# BHOnOfreSquareBoard.net
KiCad netlist of a schematic drawn in EAGLE
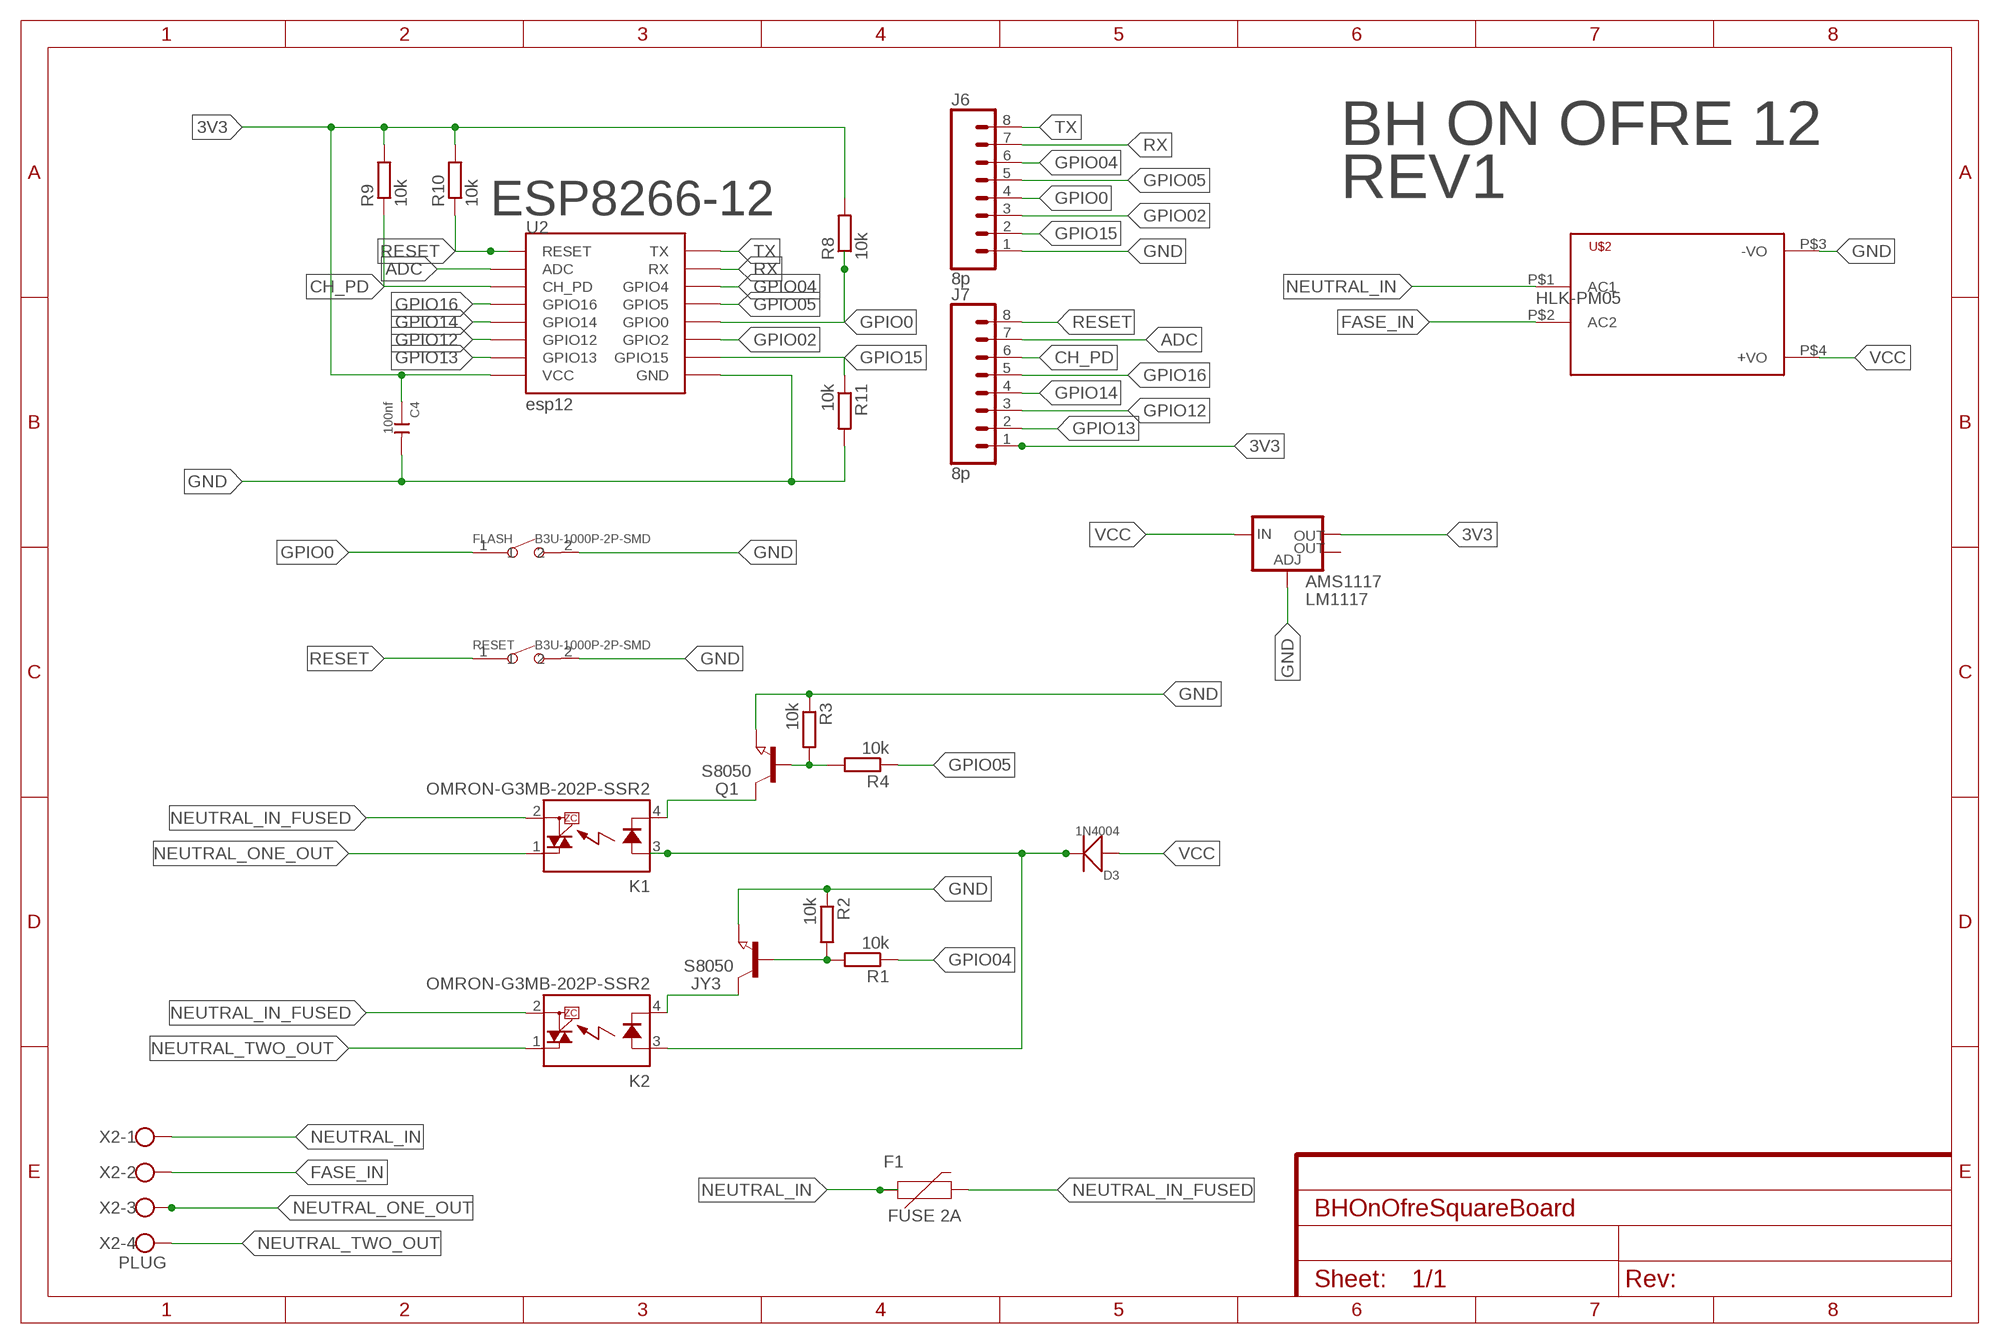
[diagram p0: schematic, sheet 1]

(export (version "E")
  (design (tool "Eeschema 10.0.6"))
  (components
    (comp (ref "AMS1117")
      (value "LM1117")
      (footprint "eagle-import:SOT223")
      (libsource (lib "eagle-import") (part "V_REG_LM1117SOT223"))
    )
    (comp (ref "C4")
      (value "100nf")
      (footprint "eagle-import:C0805")
      (fields (field (name "MPN") "CC0805KRX7R9BB104"))
      (libsource (lib "eagle-import") (part "CERAMIC-100NF-50V-10%-X7R(0805)"))
    )
    (comp (ref "D3")
      (value "1N4004")
      (footprint "eagle-import:DO-214AC")
      (fields (field (name "MPN") "1N4007"))
      (libsource (lib "eagle-import") (part "DIODE-GEN-PURPOSE-1KV-1A(DO-214AC)"))
    )
    (comp (ref "F1")
      (value "FUSE 2A")
      (footprint "eagle-import:PTH")
      (libsource (lib "eagle-import") (part "PPTC_PTH"))
    )
    (comp (ref "FLASH")
      (value "B3U-1000P-2P-SMD")
      (footprint "eagle-import:SW2-2.6-3.0X2.5X1.2+0.4MM")
      (libsource (lib "eagle-import") (part "SMD-BUTTON(2P-3.0X2.5X1.2+0.4MM)-B3U-1000P-2P-SMD"))
    )
    (comp (ref "J6")
      (value "8p")
      (footprint "eagle-import:1X08")
      (libsource (lib "eagle-import") (part "CONN_08{dblquote}"))
    )
    (comp (ref "J7")
      (value "8p")
      (footprint "eagle-import:1X08")
      (libsource (lib "eagle-import") (part "CONN_08{dblquote}"))
    )
    (comp (ref "JY3")
      (value "S8050")
      (footprint "eagle-import:SOT23")
      (libsource (lib "eagle-import") (part "NPN-TRANSISTOR_SOT23"))
    )
    (comp (ref "K1")
      (value "OMRON-G3MB-202P-SSR2")
      (footprint "eagle-import:OMRON-G3MB-202P-SSR")
      (fields (field (name "MPN") "S202S02F"))
      (libsource (lib "eagle-import") (part "OMRON-G3MB-202P-SSR2"))
    )
    (comp (ref "K2")
      (value "OMRON-G3MB-202P-SSR2")
      (footprint "eagle-import:OMRON-G3MB-202P-SSR")
      (fields (field (name "MPN") "S202S02F"))
      (libsource (lib "eagle-import") (part "OMRON-G3MB-202P-SSR2"))
    )
    (comp (ref "Q1")
      (value "S8050")
      (footprint "eagle-import:SOT23")
      (libsource (lib "eagle-import") (part "NPN-TRANSISTOR_SOT23"))
    )
    (comp (ref "R1")
      (value "10k")
      (footprint "eagle-import:R0603")
      (libsource (lib "eagle-import") (part "R-EU_R0603"))
    )
    (comp (ref "R2")
      (value "10k")
      (footprint "eagle-import:R0603")
      (libsource (lib "eagle-import") (part "R-EU_R0603"))
    )
    (comp (ref "R3")
      (value "10k")
      (footprint "eagle-import:R0603")
      (libsource (lib "eagle-import") (part "R-EU_R0603"))
    )
    (comp (ref "R4")
      (value "10k")
      (footprint "eagle-import:R0603")
      (libsource (lib "eagle-import") (part "R-EU_R0603"))
    )
    (comp (ref "R8")
      (value "10k")
      (footprint "eagle-import:R0603")
      (libsource (lib "eagle-import") (part "R-EU_R0603"))
    )
    (comp (ref "R9")
      (value "10k")
      (footprint "eagle-import:R0603")
      (libsource (lib "eagle-import") (part "R-EU_R0603"))
    )
    (comp (ref "R10")
      (value "10k")
      (footprint "eagle-import:R0603")
      (libsource (lib "eagle-import") (part "R-EU_R0603"))
    )
    (comp (ref "R11")
      (value "10k")
      (footprint "eagle-import:R0603")
      (libsource (lib "eagle-import") (part "R-EU_R0603"))
    )
    (comp (ref "RESET")
      (value "B3U-1000P-2P-SMD")
      (footprint "eagle-import:SW2-2.6-3.0X2.5X1.2+0.4MM")
      (libsource (lib "eagle-import") (part "SMD-BUTTON(2P-3.0X2.5X1.2+0.4MM)-B3U-1000P-2P-SMD"))
    )
    (comp (ref "U$2")
      (value "HKLPM01")
      (footprint "eagle-import:HKLPM01")
      (libsource (lib "eagle-import") (part "HKLPM01"))
    )
    (comp (ref "U2")
      (value "esp12")
      (footprint "eagle-import:ESP12-SMD")
      (libsource (lib "eagle-import") (part "ESP12SMD"))
    )
    (comp (ref "X2")
      (value "PLUG")
      (footprint "eagle-import:W237-4")
      (libsource (lib "eagle-import") (part "W237-4"))
    )
  )
  (nets
    (net (code "1") (name "3V3") (class "Default")
      (node (ref "AMS1117") (pin "2") (pinfunction "OUT_2") (pintype "output"))
      (node (ref "C4") (pin "1") (pinfunction "1_1") (pintype "passive"))
      (node (ref "J7") (pin "1") (pinfunction "1_1") (pintype "passive"))
      (node (ref "R10") (pin "2") (pinfunction "2_2") (pintype "passive"))
      (node (ref "R8") (pin "2") (pinfunction "2_2") (pintype "passive"))
      (node (ref "R9") (pin "2") (pinfunction "2_2") (pintype "passive"))
      (node (ref "U2") (pin "VCC") (pinfunction "VCC_VCC") (pintype "bidirectional"))
    )
    (net (code "2") (name "ADC") (class "Default")
      (node (ref "J7") (pin "7") (pinfunction "7_7") (pintype "passive"))
      (node (ref "U2") (pin "ADC") (pinfunction "ADC_ADC") (pintype "bidirectional"))
    )
    (net (code "3") (name "CH_PD") (class "Default")
      (node (ref "J7") (pin "6") (pinfunction "6_6") (pintype "passive"))
      (node (ref "R9") (pin "1") (pinfunction "1_1") (pintype "passive"))
      (node (ref "U2") (pin "CH_PD") (pinfunction "CH_PD_CH_PD") (pintype "bidirectional"))
    )
    (net (code "4") (name "FASE_IN") (class "Default")
      (node (ref "U$2") (pin "P$2") (pinfunction "AC2_P$2") (pintype "bidirectional"))
      (node (ref "X2") (pin "2") (pinfunction "KL_2") (pintype "passive"))
    )
    (net (code "5") (name "GND") (class "Default")
      (node (ref "AMS1117") (pin "1") (pinfunction "ADJ_1") (pintype "input"))
      (node (ref "C4") (pin "2") (pinfunction "2_2") (pintype "passive"))
      (node (ref "FLASH") (pin "2") (pinfunction "2_2") (pintype "bidirectional"))
      (node (ref "J6") (pin "1") (pinfunction "1_1") (pintype "passive"))
      (node (ref "JY3") (pin "2") (pinfunction "E_2") (pintype "passive"))
      (node (ref "Q1") (pin "2") (pinfunction "E_2") (pintype "passive"))
      (node (ref "R11") (pin "2") (pinfunction "2_2") (pintype "passive"))
      (node (ref "R2") (pin "1") (pinfunction "1_1") (pintype "passive"))
      (node (ref "R3") (pin "1") (pinfunction "1_1") (pintype "passive"))
      (node (ref "RESET") (pin "2") (pinfunction "2_2") (pintype "bidirectional"))
      (node (ref "U$2") (pin "P$3") (pinfunction "-VO_P$3") (pintype "bidirectional"))
      (node (ref "U2") (pin "GND") (pinfunction "GND_GND") (pintype "bidirectional"))
    )
    (net (code "6") (name "GPIO0") (class "Default")
      (node (ref "FLASH") (pin "1") (pinfunction "1_1") (pintype "bidirectional"))
      (node (ref "J6") (pin "4") (pinfunction "4_4") (pintype "passive"))
      (node (ref "R8") (pin "1") (pinfunction "1_1") (pintype "passive"))
      (node (ref "U2") (pin "GPIO0") (pinfunction "GPIO0_GPIO0") (pintype "bidirectional"))
    )
    (net (code "7") (name "GPIO02") (class "Default")
      (node (ref "J6") (pin "3") (pinfunction "3_3") (pintype "passive"))
      (node (ref "U2") (pin "GPIO2") (pinfunction "GPIO2_GPIO2") (pintype "bidirectional"))
    )
    (net (code "8") (name "GPIO04") (class "Default")
      (node (ref "J6") (pin "6") (pinfunction "6_6") (pintype "passive"))
      (node (ref "R1") (pin "1") (pinfunction "1_1") (pintype "passive"))
      (node (ref "U2") (pin "GPIO4") (pinfunction "GPIO4_GPIO4") (pintype "bidirectional"))
    )
    (net (code "9") (name "GPIO05") (class "Default")
      (node (ref "J6") (pin "5") (pinfunction "5_5") (pintype "passive"))
      (node (ref "R4") (pin "1") (pinfunction "1_1") (pintype "passive"))
      (node (ref "U2") (pin "GPIO5") (pinfunction "GPIO5_GPIO5") (pintype "bidirectional"))
    )
    (net (code "10") (name "GPIO12") (class "Default")
      (node (ref "J7") (pin "3") (pinfunction "3_3") (pintype "passive"))
      (node (ref "U2") (pin "GPIO12") (pinfunction "GPIO12_GPIO12") (pintype "bidirectional"))
    )
    (net (code "11") (name "GPIO13") (class "Default")
      (node (ref "J7") (pin "2") (pinfunction "2_2") (pintype "passive"))
      (node (ref "U2") (pin "GPIO13") (pinfunction "GPIO13_GPIO13") (pintype "bidirectional"))
    )
    (net (code "12") (name "GPIO14") (class "Default")
      (node (ref "J7") (pin "4") (pinfunction "4_4") (pintype "passive"))
      (node (ref "U2") (pin "GPIO14") (pinfunction "GPIO14_GPIO14") (pintype "bidirectional"))
    )
    (net (code "13") (name "GPIO15") (class "Default")
      (node (ref "J6") (pin "2") (pinfunction "2_2") (pintype "passive"))
      (node (ref "R11") (pin "1") (pinfunction "1_1") (pintype "passive"))
      (node (ref "U2") (pin "GPIO15") (pinfunction "GPIO15_GPIO15") (pintype "bidirectional"))
    )
    (net (code "14") (name "GPIO16") (class "Default")
      (node (ref "J7") (pin "5") (pinfunction "5_5") (pintype "passive"))
      (node (ref "U2") (pin "GPIO16") (pinfunction "GPIO16_GPIO16") (pintype "bidirectional"))
    )
    (net (code "15") (name "NEUTRAL_IN") (class "Default")
      (node (ref "F1") (pin "P$1") (pinfunction "1_P$1") (pintype "bidirectional"))
      (node (ref "U$2") (pin "P$1") (pinfunction "AC1_P$1") (pintype "bidirectional"))
      (node (ref "X2") (pin "1") (pinfunction "KL_1") (pintype "passive"))
    )
    (net (code "16") (name "NEUTRAL_IN_FUSED") (class "Default")
      (node (ref "F1") (pin "P$2") (pinfunction "2_P$2") (pintype "bidirectional"))
      (node (ref "K1") (pin "2") (pinfunction "DS2_2") (pintype "passive"))
      (node (ref "K2") (pin "2") (pinfunction "DS2_2") (pintype "passive"))
    )
    (net (code "17") (name "NEUTRAL_ONE_OUT") (class "Default")
      (node (ref "K1") (pin "1") (pinfunction "DS1_1") (pintype "passive"))
      (node (ref "X2") (pin "3") (pinfunction "KL_3") (pintype "passive"))
    )
    (net (code "18") (name "NEUTRAL_TWO_OUT") (class "Default")
      (node (ref "K2") (pin "1") (pinfunction "DS1_1") (pintype "passive"))
      (node (ref "X2") (pin "4") (pinfunction "KL_4") (pintype "passive"))
    )
    (net (code "19") (name "Net-(D3--)") (class "Default")
      (node (ref "D3") (pin "2") (pinfunction "-_2") (pintype "passive"))
      (node (ref "K1") (pin "3") (pinfunction "A_3") (pintype "passive"))
      (node (ref "K2") (pin "3") (pinfunction "A_3") (pintype "passive"))
    )
    (net (code "20") (name "Net-(JY3-B)") (class "Default")
      (node (ref "JY3") (pin "1") (pinfunction "B_1") (pintype "passive"))
      (node (ref "R1") (pin "2") (pinfunction "2_2") (pintype "passive"))
      (node (ref "R2") (pin "2") (pinfunction "2_2") (pintype "passive"))
    )
    (net (code "21") (name "Net-(JY3-C)") (class "Default")
      (node (ref "JY3") (pin "3") (pinfunction "C_3") (pintype "passive"))
      (node (ref "K2") (pin "4") (pinfunction "K_4") (pintype "passive"))
    )
    (net (code "22") (name "Net-(K1-K)") (class "Default")
      (node (ref "K1") (pin "4") (pinfunction "K_4") (pintype "passive"))
      (node (ref "Q1") (pin "3") (pinfunction "C_3") (pintype "passive"))
    )
    (net (code "23") (name "Net-(Q1-B)") (class "Default")
      (node (ref "Q1") (pin "1") (pinfunction "B_1") (pintype "passive"))
      (node (ref "R3") (pin "2") (pinfunction "2_2") (pintype "passive"))
      (node (ref "R4") (pin "2") (pinfunction "2_2") (pintype "passive"))
    )
    (net (code "24") (name "RESET") (class "Default")
      (node (ref "J7") (pin "8") (pinfunction "8_8") (pintype "passive"))
      (node (ref "R10") (pin "1") (pinfunction "1_1") (pintype "passive"))
      (node (ref "RESET") (pin "1") (pinfunction "1_1") (pintype "bidirectional"))
      (node (ref "U2") (pin "RESET") (pinfunction "RESET_RESET") (pintype "bidirectional"))
    )
    (net (code "25") (name "RX") (class "Default")
      (node (ref "J6") (pin "7") (pinfunction "7_7") (pintype "passive"))
      (node (ref "U2") (pin "RXD0") (pinfunction "RX_RXD0") (pintype "bidirectional"))
    )
    (net (code "26") (name "TX") (class "Default")
      (node (ref "J6") (pin "8") (pinfunction "8_8") (pintype "passive"))
      (node (ref "U2") (pin "TXD0") (pinfunction "TX_TXD0") (pintype "bidirectional"))
    )
    (net (code "27") (name "VCC") (class "Default")
      (node (ref "AMS1117") (pin "3") (pinfunction "IN_3") (pintype "input"))
      (node (ref "D3") (pin "1") (pinfunction "+_1") (pintype "passive"))
      (node (ref "U$2") (pin "P$4") (pinfunction "+VO_P$4") (pintype "bidirectional"))
    )
    (net (code "28") (name "unconnected-(AMS1117-OUT-Pad4)") (class "Default")
      (node (ref "AMS1117") (pin "4") (pinfunction "OUT_4") (pintype "output"))
    )
  )
)
